# ext_board.net
KiCad netlist of a schematic drawn in EAGLE
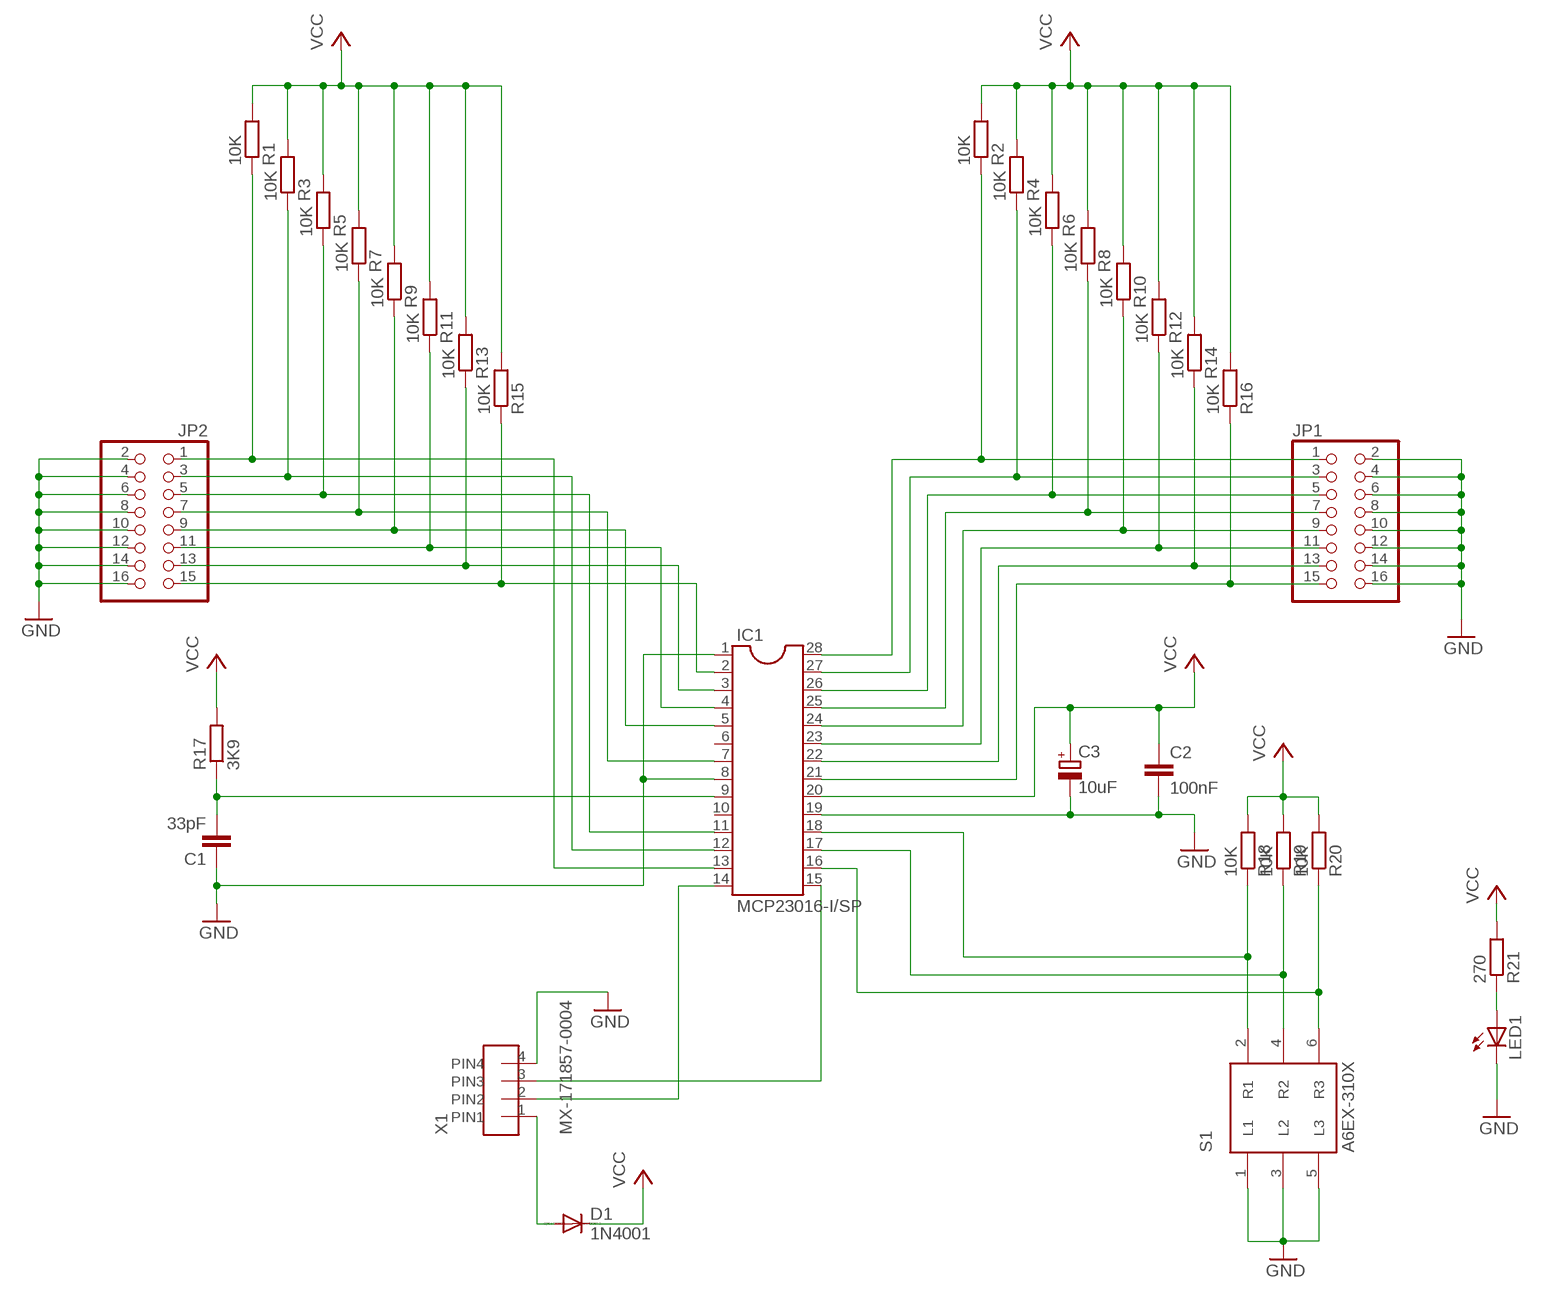
[diagram p0: schematic, sheet 1]

(export (version "E")
  (design (tool "Eeschema 10.0.6"))
  (components
    (comp (ref "C1")
      (value "33pF")
      (footprint "eagle-import:C050-030X075")
      (libsource (lib "eagle-import") (part "C-EU050-030X075"))
    )
    (comp (ref "C2")
      (value "100nF")
      (footprint "eagle-import:C050-030X075")
      (libsource (lib "eagle-import") (part "C-EU050-030X075"))
    )
    (comp (ref "C3")
      (value "10uF")
      (footprint "eagle-import:E2,5-7")
      (libsource (lib "eagle-import") (part "CPOL-EUE2.5-7"))
    )
    (comp (ref "D1")
      (value "1N4001")
      (footprint "eagle-import:DO41-10")
      (libsource (lib "eagle-import") (part "1N4004"))
    )
    (comp (ref "IC1")
      (value "MCP23016-I/SP")
      (footprint "eagle-import:DIL28-3")
      (libsource (lib "eagle-import") (part "DIL28-3"))
    )
    (comp (ref "JP1")
      (value "PINHD-2X8")
      (footprint "eagle-import:2X08")
      (libsource (lib "eagle-import") (part "PINHD-2X8"))
    )
    (comp (ref "JP2")
      (value "PINHD-2X8")
      (footprint "eagle-import:2X08")
      (libsource (lib "eagle-import") (part "PINHD-2X8"))
    )
    (comp (ref "LED1")
      (value "LED3MM")
      (footprint "eagle-import:LED3MM")
      (libsource (lib "eagle-import") (part "LED3MM"))
    )
    (comp (ref "R1")
      (value "10K")
      (footprint "eagle-import:0204_7")
      (libsource (lib "eagle-import") (part "R-EU_0204/7"))
    )
    (comp (ref "R2")
      (value "10K")
      (footprint "eagle-import:0204_7")
      (libsource (lib "eagle-import") (part "R-EU_0204/7"))
    )
    (comp (ref "R3")
      (value "10K")
      (footprint "eagle-import:0204_7")
      (libsource (lib "eagle-import") (part "R-EU_0204/7"))
    )
    (comp (ref "R4")
      (value "10K")
      (footprint "eagle-import:0204_7")
      (libsource (lib "eagle-import") (part "R-EU_0204/7"))
    )
    (comp (ref "R5")
      (value "10K")
      (footprint "eagle-import:0204_7")
      (libsource (lib "eagle-import") (part "R-EU_0204/7"))
    )
    (comp (ref "R6")
      (value "10K")
      (footprint "eagle-import:0204_7")
      (libsource (lib "eagle-import") (part "R-EU_0204/7"))
    )
    (comp (ref "R7")
      (value "10K")
      (footprint "eagle-import:0204_7")
      (libsource (lib "eagle-import") (part "R-EU_0204/7"))
    )
    (comp (ref "R8")
      (value "10K")
      (footprint "eagle-import:0204_7")
      (libsource (lib "eagle-import") (part "R-EU_0204/7"))
    )
    (comp (ref "R9")
      (value "10K")
      (footprint "eagle-import:0204_7")
      (libsource (lib "eagle-import") (part "R-EU_0204/7"))
    )
    (comp (ref "R10")
      (value "10K")
      (footprint "eagle-import:0204_7")
      (libsource (lib "eagle-import") (part "R-EU_0204/7"))
    )
    (comp (ref "R11")
      (value "10K")
      (footprint "eagle-import:0204_7")
      (libsource (lib "eagle-import") (part "R-EU_0204/7"))
    )
    (comp (ref "R12")
      (value "10K")
      (footprint "eagle-import:0204_7")
      (libsource (lib "eagle-import") (part "R-EU_0204/7"))
    )
    (comp (ref "R13")
      (value "10K")
      (footprint "eagle-import:0204_7")
      (libsource (lib "eagle-import") (part "R-EU_0204/7"))
    )
    (comp (ref "R14")
      (value "10K")
      (footprint "eagle-import:0204_7")
      (libsource (lib "eagle-import") (part "R-EU_0204/7"))
    )
    (comp (ref "R15")
      (value "10K")
      (footprint "eagle-import:0204_7")
      (libsource (lib "eagle-import") (part "R-EU_0204/7"))
    )
    (comp (ref "R16")
      (value "10K")
      (footprint "eagle-import:0204_7")
      (libsource (lib "eagle-import") (part "R-EU_0204/7"))
    )
    (comp (ref "R17")
      (value "3K9")
      (footprint "eagle-import:0204_7")
      (libsource (lib "eagle-import") (part "R-EU_0204/7"))
    )
    (comp (ref "R18")
      (value "10K")
      (footprint "eagle-import:0204_7")
      (libsource (lib "eagle-import") (part "R-EU_0204/7"))
    )
    (comp (ref "R19")
      (value "10K")
      (footprint "eagle-import:0204_7")
      (libsource (lib "eagle-import") (part "R-EU_0204/7"))
    )
    (comp (ref "R20")
      (value "10K")
      (footprint "eagle-import:0204_7")
      (libsource (lib "eagle-import") (part "R-EU_0204/7"))
    )
    (comp (ref "R21")
      (value "270")
      (footprint "eagle-import:0204_7")
      (libsource (lib "eagle-import") (part "R-EU_0204/7"))
    )
    (comp (ref "S1")
      (value "A6EX-310X")
      (footprint "eagle-import:A6EX-310X")
      (libsource (lib "eagle-import") (part "A6EX-310X"))
    )
    (comp (ref "X1")
      (value "MX-171857-0004")
      (footprint "eagle-import:MX-171857-0004")
      (libsource (lib "eagle-import") (part "MX-171857-0004"))
    )
  )
  (nets
    (net (code "1") (name "GND") (class "Default")
      (node (ref "C1") (pin "1") (pinfunction "1_1") (pintype "passive"))
      (node (ref "C2") (pin "2") (pinfunction "2_2") (pintype "passive"))
      (node (ref "C3") (pin "-") (pinfunction "-_-") (pintype "passive"))
      (node (ref "IC1") (pin "1") (pinfunction "1_1") (pintype "passive"))
      (node (ref "IC1") (pin "19") (pinfunction "19_19") (pintype "passive"))
      (node (ref "IC1") (pin "8") (pinfunction "8_8") (pintype "passive"))
      (node (ref "JP1") (pin "10") (pinfunction "10_10") (pintype "passive"))
      (node (ref "JP1") (pin "12") (pinfunction "12_12") (pintype "passive"))
      (node (ref "JP1") (pin "14") (pinfunction "14_14") (pintype "passive"))
      (node (ref "JP1") (pin "16") (pinfunction "16_16") (pintype "passive"))
      (node (ref "JP1") (pin "2") (pinfunction "2_2") (pintype "passive"))
      (node (ref "JP1") (pin "4") (pinfunction "4_4") (pintype "passive"))
      (node (ref "JP1") (pin "6") (pinfunction "6_6") (pintype "passive"))
      (node (ref "JP1") (pin "8") (pinfunction "8_8") (pintype "passive"))
      (node (ref "JP2") (pin "10") (pinfunction "10_10") (pintype "passive"))
      (node (ref "JP2") (pin "12") (pinfunction "12_12") (pintype "passive"))
      (node (ref "JP2") (pin "14") (pinfunction "14_14") (pintype "passive"))
      (node (ref "JP2") (pin "16") (pinfunction "16_16") (pintype "passive"))
      (node (ref "JP2") (pin "2") (pinfunction "2_2") (pintype "passive"))
      (node (ref "JP2") (pin "4") (pinfunction "4_4") (pintype "passive"))
      (node (ref "JP2") (pin "6") (pinfunction "6_6") (pintype "passive"))
      (node (ref "JP2") (pin "8") (pinfunction "8_8") (pintype "passive"))
      (node (ref "LED1") (pin "K") (pinfunction "C_K") (pintype "passive"))
      (node (ref "S1") (pin "1") (pinfunction "L1_1") (pintype "bidirectional"))
      (node (ref "S1") (pin "3") (pinfunction "L2_3") (pintype "bidirectional"))
      (node (ref "S1") (pin "5") (pinfunction "L3_5") (pintype "bidirectional"))
      (node (ref "X1") (pin "4") (pinfunction "PIN4_4") (pintype "bidirectional"))
    )
    (net (code "2") (name "Net-(C1-Pad2)") (class "Default")
      (node (ref "C1") (pin "2") (pinfunction "2_2") (pintype "passive"))
      (node (ref "IC1") (pin "9") (pinfunction "9_9") (pintype "passive"))
      (node (ref "R17") (pin "1") (pinfunction "1_1") (pintype "passive"))
    )
    (net (code "3") (name "Net-(IC1-Pad2)") (class "Default")
      (node (ref "IC1") (pin "2") (pinfunction "2_2") (pintype "passive"))
      (node (ref "JP2") (pin "15") (pinfunction "15_15") (pintype "passive"))
      (node (ref "R15") (pin "1") (pinfunction "1_1") (pintype "passive"))
    )
    (net (code "4") (name "Net-(IC1-Pad3)") (class "Default")
      (node (ref "IC1") (pin "3") (pinfunction "3_3") (pintype "passive"))
      (node (ref "JP2") (pin "13") (pinfunction "13_13") (pintype "passive"))
      (node (ref "R13") (pin "1") (pinfunction "1_1") (pintype "passive"))
    )
    (net (code "5") (name "Net-(IC1-Pad4)") (class "Default")
      (node (ref "IC1") (pin "4") (pinfunction "4_4") (pintype "passive"))
      (node (ref "JP2") (pin "11") (pinfunction "11_11") (pintype "passive"))
      (node (ref "R11") (pin "1") (pinfunction "1_1") (pintype "passive"))
    )
    (net (code "6") (name "Net-(IC1-Pad5)") (class "Default")
      (node (ref "IC1") (pin "5") (pinfunction "5_5") (pintype "passive"))
      (node (ref "JP2") (pin "9") (pinfunction "9_9") (pintype "passive"))
      (node (ref "R9") (pin "1") (pinfunction "1_1") (pintype "passive"))
    )
    (net (code "7") (name "Net-(IC1-Pad7)") (class "Default")
      (node (ref "IC1") (pin "7") (pinfunction "7_7") (pintype "passive"))
      (node (ref "JP2") (pin "7") (pinfunction "7_7") (pintype "passive"))
      (node (ref "R7") (pin "1") (pinfunction "1_1") (pintype "passive"))
    )
    (net (code "8") (name "Net-(IC1-Pad11)") (class "Default")
      (node (ref "IC1") (pin "11") (pinfunction "11_11") (pintype "passive"))
      (node (ref "JP2") (pin "5") (pinfunction "5_5") (pintype "passive"))
      (node (ref "R5") (pin "1") (pinfunction "1_1") (pintype "passive"))
    )
    (net (code "9") (name "Net-(IC1-Pad12)") (class "Default")
      (node (ref "IC1") (pin "12") (pinfunction "12_12") (pintype "passive"))
      (node (ref "JP2") (pin "3") (pinfunction "3_3") (pintype "passive"))
      (node (ref "R3") (pin "1") (pinfunction "1_1") (pintype "passive"))
    )
    (net (code "10") (name "Net-(IC1-Pad13)") (class "Default")
      (node (ref "IC1") (pin "13") (pinfunction "13_13") (pintype "passive"))
      (node (ref "JP2") (pin "1") (pinfunction "1_1") (pintype "passive"))
      (node (ref "R1") (pin "1") (pinfunction "1_1") (pintype "passive"))
    )
    (net (code "11") (name "Net-(IC1-Pad21)") (class "Default")
      (node (ref "IC1") (pin "21") (pinfunction "21_21") (pintype "passive"))
      (node (ref "JP1") (pin "15") (pinfunction "15_15") (pintype "passive"))
      (node (ref "R16") (pin "1") (pinfunction "1_1") (pintype "passive"))
    )
    (net (code "12") (name "Net-(IC1-Pad22)") (class "Default")
      (node (ref "IC1") (pin "22") (pinfunction "22_22") (pintype "passive"))
      (node (ref "JP1") (pin "13") (pinfunction "13_13") (pintype "passive"))
      (node (ref "R14") (pin "1") (pinfunction "1_1") (pintype "passive"))
    )
    (net (code "13") (name "Net-(IC1-Pad23)") (class "Default")
      (node (ref "IC1") (pin "23") (pinfunction "23_23") (pintype "passive"))
      (node (ref "JP1") (pin "11") (pinfunction "11_11") (pintype "passive"))
      (node (ref "R12") (pin "1") (pinfunction "1_1") (pintype "passive"))
    )
    (net (code "14") (name "Net-(IC1-Pad24)") (class "Default")
      (node (ref "IC1") (pin "24") (pinfunction "24_24") (pintype "passive"))
      (node (ref "JP1") (pin "9") (pinfunction "9_9") (pintype "passive"))
      (node (ref "R10") (pin "1") (pinfunction "1_1") (pintype "passive"))
    )
    (net (code "15") (name "Net-(IC1-Pad25)") (class "Default")
      (node (ref "IC1") (pin "25") (pinfunction "25_25") (pintype "passive"))
      (node (ref "JP1") (pin "7") (pinfunction "7_7") (pintype "passive"))
      (node (ref "R8") (pin "1") (pinfunction "1_1") (pintype "passive"))
    )
    (net (code "16") (name "Net-(IC1-Pad26)") (class "Default")
      (node (ref "IC1") (pin "26") (pinfunction "26_26") (pintype "passive"))
      (node (ref "JP1") (pin "5") (pinfunction "5_5") (pintype "passive"))
      (node (ref "R6") (pin "1") (pinfunction "1_1") (pintype "passive"))
    )
    (net (code "17") (name "Net-(IC1-Pad27)") (class "Default")
      (node (ref "IC1") (pin "27") (pinfunction "27_27") (pintype "passive"))
      (node (ref "JP1") (pin "3") (pinfunction "3_3") (pintype "passive"))
      (node (ref "R4") (pin "1") (pinfunction "1_1") (pintype "passive"))
    )
    (net (code "18") (name "Net-(IC1-Pad28)") (class "Default")
      (node (ref "IC1") (pin "28") (pinfunction "28_28") (pintype "passive"))
      (node (ref "JP1") (pin "1") (pinfunction "1_1") (pintype "passive"))
      (node (ref "R2") (pin "1") (pinfunction "1_1") (pintype "passive"))
    )
    (net (code "19") (name "Net-(LED1-PadA)") (class "Default")
      (node (ref "LED1") (pin "A") (pinfunction "A_A") (pintype "passive"))
      (node (ref "R21") (pin "1") (pinfunction "1_1") (pintype "passive"))
    )
    (net (code "20") (name "Net-(S1-R1)") (class "Default")
      (node (ref "IC1") (pin "18") (pinfunction "18_18") (pintype "passive"))
      (node (ref "R18") (pin "1") (pinfunction "1_1") (pintype "passive"))
      (node (ref "S1") (pin "2") (pinfunction "R1_2") (pintype "bidirectional"))
    )
    (net (code "21") (name "Net-(S1-R2)") (class "Default")
      (node (ref "IC1") (pin "17") (pinfunction "17_17") (pintype "passive"))
      (node (ref "R19") (pin "1") (pinfunction "1_1") (pintype "passive"))
      (node (ref "S1") (pin "4") (pinfunction "R2_4") (pintype "bidirectional"))
    )
    (net (code "22") (name "Net-(S1-R3)") (class "Default")
      (node (ref "IC1") (pin "16") (pinfunction "16_16") (pintype "passive"))
      (node (ref "R20") (pin "1") (pinfunction "1_1") (pintype "passive"))
      (node (ref "S1") (pin "6") (pinfunction "R3_6") (pintype "bidirectional"))
    )
    (net (code "23") (name "Net-(X1-PIN1)") (class "Default")
      (node (ref "D1") (pin "A") (pinfunction "A_A") (pintype "passive"))
      (node (ref "X1") (pin "1") (pinfunction "PIN1_1") (pintype "bidirectional"))
    )
    (net (code "24") (name "Net-(X1-PIN2)") (class "Default")
      (node (ref "IC1") (pin "14") (pinfunction "14_14") (pintype "passive"))
      (node (ref "X1") (pin "2") (pinfunction "PIN2_2") (pintype "bidirectional"))
    )
    (net (code "25") (name "Net-(X1-PIN3)") (class "Default")
      (node (ref "IC1") (pin "15") (pinfunction "15_15") (pintype "passive"))
      (node (ref "X1") (pin "3") (pinfunction "PIN3_3") (pintype "bidirectional"))
    )
    (net (code "26") (name "VCC") (class "Default")
      (node (ref "C2") (pin "1") (pinfunction "1_1") (pintype "passive"))
      (node (ref "C3") (pin "+") (pinfunction "+_+") (pintype "passive"))
      (node (ref "D1") (pin "C") (pinfunction "C_C") (pintype "passive"))
      (node (ref "IC1") (pin "20") (pinfunction "20_20") (pintype "passive"))
      (node (ref "R1") (pin "2") (pinfunction "2_2") (pintype "passive"))
      (node (ref "R10") (pin "2") (pinfunction "2_2") (pintype "passive"))
      (node (ref "R11") (pin "2") (pinfunction "2_2") (pintype "passive"))
      (node (ref "R12") (pin "2") (pinfunction "2_2") (pintype "passive"))
      (node (ref "R13") (pin "2") (pinfunction "2_2") (pintype "passive"))
      (node (ref "R14") (pin "2") (pinfunction "2_2") (pintype "passive"))
      (node (ref "R15") (pin "2") (pinfunction "2_2") (pintype "passive"))
      (node (ref "R16") (pin "2") (pinfunction "2_2") (pintype "passive"))
      (node (ref "R17") (pin "2") (pinfunction "2_2") (pintype "passive"))
      (node (ref "R18") (pin "2") (pinfunction "2_2") (pintype "passive"))
      (node (ref "R19") (pin "2") (pinfunction "2_2") (pintype "passive"))
      (node (ref "R2") (pin "2") (pinfunction "2_2") (pintype "passive"))
      (node (ref "R20") (pin "2") (pinfunction "2_2") (pintype "passive"))
      (node (ref "R21") (pin "2") (pinfunction "2_2") (pintype "passive"))
      (node (ref "R3") (pin "2") (pinfunction "2_2") (pintype "passive"))
      (node (ref "R4") (pin "2") (pinfunction "2_2") (pintype "passive"))
      (node (ref "R5") (pin "2") (pinfunction "2_2") (pintype "passive"))
      (node (ref "R6") (pin "2") (pinfunction "2_2") (pintype "passive"))
      (node (ref "R7") (pin "2") (pinfunction "2_2") (pintype "passive"))
      (node (ref "R8") (pin "2") (pinfunction "2_2") (pintype "passive"))
      (node (ref "R9") (pin "2") (pinfunction "2_2") (pintype "passive"))
    )
    (net (code "27") (name "unconnected-(IC1-Pad6)") (class "Default")
      (node (ref "IC1") (pin "6") (pinfunction "6_6") (pintype "passive"))
    )
    (net (code "28") (name "unconnected-(IC1-Pad10)") (class "Default")
      (node (ref "IC1") (pin "10") (pinfunction "10_10") (pintype "passive"))
    )
  )
)
